# R212F.net
KiCad netlist of a schematic drawn in EAGLE
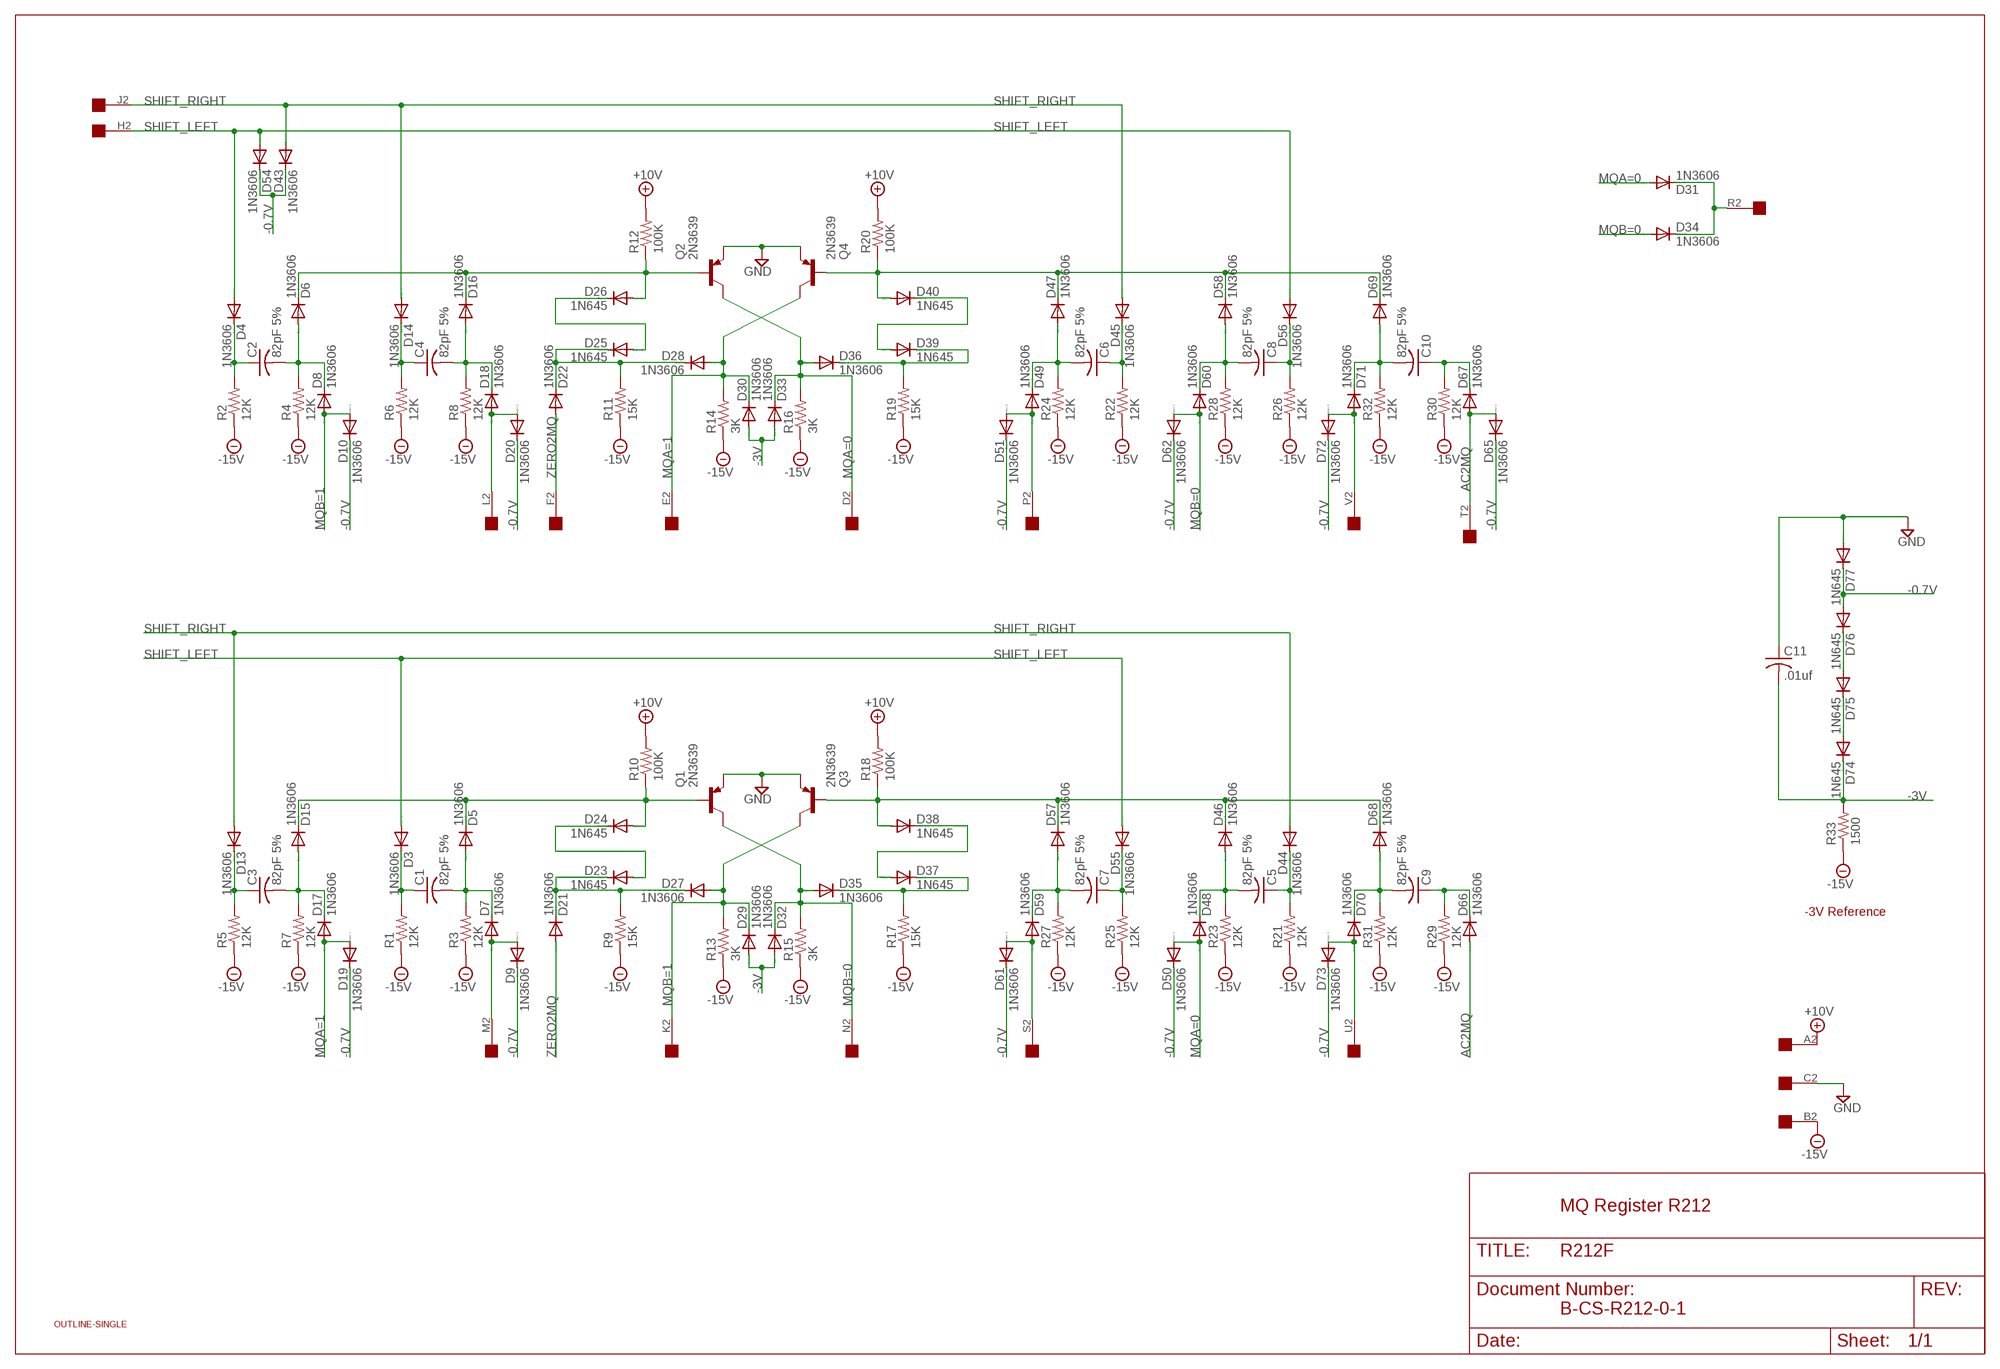
[diagram p0: schematic, sheet 1]

(export (version "E")
  (design (tool "Eeschema 10.0.6"))
  (components
    (comp (ref "C1")
      (value "82pF 5%")
      (footprint "eagle-import:C050-025X075")
      (libsource (lib "eagle-import") (part "C-US050-025X075"))
    )
    (comp (ref "C2")
      (value "82pF 5%")
      (footprint "eagle-import:C050-025X075")
      (libsource (lib "eagle-import") (part "C-US050-025X075"))
    )
    (comp (ref "C3")
      (value "82pF 5%")
      (footprint "eagle-import:C050-025X075")
      (libsource (lib "eagle-import") (part "C-US050-025X075"))
    )
    (comp (ref "C4")
      (value "82pF 5%")
      (footprint "eagle-import:C050-025X075")
      (libsource (lib "eagle-import") (part "C-US050-025X075"))
    )
    (comp (ref "C5")
      (value "82pF 5%")
      (footprint "eagle-import:C050-025X075")
      (libsource (lib "eagle-import") (part "C-US050-025X075"))
    )
    (comp (ref "C6")
      (value "82pF 5%")
      (footprint "eagle-import:C050-025X075")
      (libsource (lib "eagle-import") (part "C-US050-025X075"))
    )
    (comp (ref "C7")
      (value "82pF 5%")
      (footprint "eagle-import:C050-025X075")
      (libsource (lib "eagle-import") (part "C-US050-025X075"))
    )
    (comp (ref "C8")
      (value "82pF 5%")
      (footprint "eagle-import:C050-025X075")
      (libsource (lib "eagle-import") (part "C-US050-025X075"))
    )
    (comp (ref "C9")
      (value "82pF 5%")
      (footprint "eagle-import:C050-025X075")
      (libsource (lib "eagle-import") (part "C-US050-025X075"))
    )
    (comp (ref "C10")
      (value "82pF 5%")
      (footprint "eagle-import:C050-025X075")
      (libsource (lib "eagle-import") (part "C-US050-025X075"))
    )
    (comp (ref "C11")
      (value ".01uf")
      (footprint "eagle-import:C050-025X075")
      (libsource (lib "eagle-import") (part "C-US050-025X075"))
    )
    (comp (ref "D3")
      (value "1N3606")
      (footprint "eagle-import:DO35-10")
      (libsource (lib "eagle-import") (part "1N4148DO35-10"))
    )
    (comp (ref "D4")
      (value "1N3606")
      (footprint "eagle-import:DO35-10")
      (libsource (lib "eagle-import") (part "1N4148DO35-10"))
    )
    (comp (ref "D5")
      (value "1N3606")
      (footprint "eagle-import:DO35-10")
      (libsource (lib "eagle-import") (part "1N4148DO35-10"))
    )
    (comp (ref "D6")
      (value "1N3606")
      (footprint "eagle-import:DO35-10")
      (libsource (lib "eagle-import") (part "1N4148DO35-10"))
    )
    (comp (ref "D7")
      (value "1N3606")
      (footprint "eagle-import:DO35-10")
      (libsource (lib "eagle-import") (part "1N4148DO35-10"))
    )
    (comp (ref "D8")
      (value "1N3606")
      (footprint "eagle-import:DO35-10")
      (libsource (lib "eagle-import") (part "1N4148DO35-10"))
    )
    (comp (ref "D9")
      (value "1N3606")
      (footprint "eagle-import:DO35-10")
      (libsource (lib "eagle-import") (part "1N4148DO35-10"))
    )
    (comp (ref "D10")
      (value "1N3606")
      (footprint "eagle-import:DO35-10")
      (libsource (lib "eagle-import") (part "1N4148DO35-10"))
    )
    (comp (ref "D13")
      (value "1N3606")
      (footprint "eagle-import:DO35-10")
      (libsource (lib "eagle-import") (part "1N4148DO35-10"))
    )
    (comp (ref "D14")
      (value "1N3606")
      (footprint "eagle-import:DO35-10")
      (libsource (lib "eagle-import") (part "1N4148DO35-10"))
    )
    (comp (ref "D15")
      (value "1N3606")
      (footprint "eagle-import:DO35-10")
      (libsource (lib "eagle-import") (part "1N4148DO35-10"))
    )
    (comp (ref "D16")
      (value "1N3606")
      (footprint "eagle-import:DO35-10")
      (libsource (lib "eagle-import") (part "1N4148DO35-10"))
    )
    (comp (ref "D17")
      (value "1N3606")
      (footprint "eagle-import:DO35-10")
      (libsource (lib "eagle-import") (part "1N4148DO35-10"))
    )
    (comp (ref "D18")
      (value "1N3606")
      (footprint "eagle-import:DO35-10")
      (libsource (lib "eagle-import") (part "1N4148DO35-10"))
    )
    (comp (ref "D19")
      (value "1N3606")
      (footprint "eagle-import:DO35-10")
      (libsource (lib "eagle-import") (part "1N4148DO35-10"))
    )
    (comp (ref "D20")
      (value "1N3606")
      (footprint "eagle-import:DO35-10")
      (libsource (lib "eagle-import") (part "1N4148DO35-10"))
    )
    (comp (ref "D21")
      (value "1N3606")
      (footprint "eagle-import:DO35-10")
      (libsource (lib "eagle-import") (part "1N4148DO35-10"))
    )
    (comp (ref "D22")
      (value "1N3606")
      (footprint "eagle-import:DO35-10")
      (libsource (lib "eagle-import") (part "1N4148DO35-10"))
    )
    (comp (ref "D23")
      (value "1N645")
      (footprint "eagle-import:DO35-10")
      (libsource (lib "eagle-import") (part "1N4148DO35-10"))
    )
    (comp (ref "D24")
      (value "1N645")
      (footprint "eagle-import:DO35-10")
      (libsource (lib "eagle-import") (part "1N4148DO35-10"))
    )
    (comp (ref "D25")
      (value "1N645")
      (footprint "eagle-import:DO35-10")
      (libsource (lib "eagle-import") (part "1N4148DO35-10"))
    )
    (comp (ref "D26")
      (value "1N645")
      (footprint "eagle-import:DO35-10")
      (libsource (lib "eagle-import") (part "1N4148DO35-10"))
    )
    (comp (ref "D27")
      (value "1N3606")
      (footprint "eagle-import:DO35-10")
      (libsource (lib "eagle-import") (part "1N4148DO35-10"))
    )
    (comp (ref "D28")
      (value "1N3606")
      (footprint "eagle-import:DO35-10")
      (libsource (lib "eagle-import") (part "1N4148DO35-10"))
    )
    (comp (ref "D29")
      (value "1N3606")
      (footprint "eagle-import:DO35-10")
      (libsource (lib "eagle-import") (part "1N4148DO35-10"))
    )
    (comp (ref "D30")
      (value "1N3606")
      (footprint "eagle-import:DO35-10")
      (libsource (lib "eagle-import") (part "1N4148DO35-10"))
    )
    (comp (ref "D31")
      (value "1N3606")
      (footprint "eagle-import:DO35-10")
      (libsource (lib "eagle-import") (part "1N4148DO35-10"))
    )
    (comp (ref "D32")
      (value "1N3606")
      (footprint "eagle-import:DO35-10")
      (libsource (lib "eagle-import") (part "1N4148DO35-10"))
    )
    (comp (ref "D33")
      (value "1N3606")
      (footprint "eagle-import:DO35-10")
      (libsource (lib "eagle-import") (part "1N4148DO35-10"))
    )
    (comp (ref "D34")
      (value "1N3606")
      (footprint "eagle-import:DO35-10")
      (libsource (lib "eagle-import") (part "1N4148DO35-10"))
    )
    (comp (ref "D35")
      (value "1N3606")
      (footprint "eagle-import:DO35-10")
      (libsource (lib "eagle-import") (part "1N4148DO35-10"))
    )
    (comp (ref "D36")
      (value "1N3606")
      (footprint "eagle-import:DO35-10")
      (libsource (lib "eagle-import") (part "1N4148DO35-10"))
    )
    (comp (ref "D37")
      (value "1N645")
      (footprint "eagle-import:DO35-10")
      (libsource (lib "eagle-import") (part "1N4148DO35-10"))
    )
    (comp (ref "D38")
      (value "1N645")
      (footprint "eagle-import:DO35-10")
      (libsource (lib "eagle-import") (part "1N4148DO35-10"))
    )
    (comp (ref "D39")
      (value "1N645")
      (footprint "eagle-import:DO35-10")
      (libsource (lib "eagle-import") (part "1N4148DO35-10"))
    )
    (comp (ref "D40")
      (value "1N645")
      (footprint "eagle-import:DO35-10")
      (libsource (lib "eagle-import") (part "1N4148DO35-10"))
    )
    (comp (ref "D43")
      (value "1N3606")
      (footprint "eagle-import:DO35-10")
      (libsource (lib "eagle-import") (part "1N4148DO35-10"))
    )
    (comp (ref "D44")
      (value "1N3606")
      (footprint "eagle-import:DO35-10")
      (libsource (lib "eagle-import") (part "1N4148DO35-10"))
    )
    (comp (ref "D45")
      (value "1N3606")
      (footprint "eagle-import:DO35-10")
      (libsource (lib "eagle-import") (part "1N4148DO35-10"))
    )
    (comp (ref "D46")
      (value "1N3606")
      (footprint "eagle-import:DO35-10")
      (libsource (lib "eagle-import") (part "1N4148DO35-10"))
    )
    (comp (ref "D47")
      (value "1N3606")
      (footprint "eagle-import:DO35-10")
      (libsource (lib "eagle-import") (part "1N4148DO35-10"))
    )
    (comp (ref "D48")
      (value "1N3606")
      (footprint "eagle-import:DO35-10")
      (libsource (lib "eagle-import") (part "1N4148DO35-10"))
    )
    (comp (ref "D49")
      (value "1N3606")
      (footprint "eagle-import:DO35-10")
      (libsource (lib "eagle-import") (part "1N4148DO35-10"))
    )
    (comp (ref "D50")
      (value "1N3606")
      (footprint "eagle-import:DO35-10")
      (libsource (lib "eagle-import") (part "1N4148DO35-10"))
    )
    (comp (ref "D51")
      (value "1N3606")
      (footprint "eagle-import:DO35-10")
      (libsource (lib "eagle-import") (part "1N4148DO35-10"))
    )
    (comp (ref "D54")
      (value "1N3606")
      (footprint "eagle-import:DO35-10")
      (libsource (lib "eagle-import") (part "1N4148DO35-10"))
    )
    (comp (ref "D55")
      (value "1N3606")
      (footprint "eagle-import:DO35-10")
      (libsource (lib "eagle-import") (part "1N4148DO35-10"))
    )
    (comp (ref "D56")
      (value "1N3606")
      (footprint "eagle-import:DO35-10")
      (libsource (lib "eagle-import") (part "1N4148DO35-10"))
    )
    (comp (ref "D57")
      (value "1N3606")
      (footprint "eagle-import:DO35-10")
      (libsource (lib "eagle-import") (part "1N4148DO35-10"))
    )
    (comp (ref "D58")
      (value "1N3606")
      (footprint "eagle-import:DO35-10")
      (libsource (lib "eagle-import") (part "1N4148DO35-10"))
    )
    (comp (ref "D59")
      (value "1N3606")
      (footprint "eagle-import:DO35-10")
      (libsource (lib "eagle-import") (part "1N4148DO35-10"))
    )
    (comp (ref "D60")
      (value "1N3606")
      (footprint "eagle-import:DO35-10")
      (libsource (lib "eagle-import") (part "1N4148DO35-10"))
    )
    (comp (ref "D61")
      (value "1N3606")
      (footprint "eagle-import:DO35-10")
      (libsource (lib "eagle-import") (part "1N4148DO35-10"))
    )
    (comp (ref "D62")
      (value "1N3606")
      (footprint "eagle-import:DO35-10")
      (libsource (lib "eagle-import") (part "1N4148DO35-10"))
    )
    (comp (ref "D65")
      (value "1N3606")
      (footprint "eagle-import:DO35-10")
      (libsource (lib "eagle-import") (part "1N4148DO35-10"))
    )
    (comp (ref "D66")
      (value "1N3606")
      (footprint "eagle-import:DO35-10")
      (libsource (lib "eagle-import") (part "1N4148DO35-10"))
    )
    (comp (ref "D67")
      (value "1N3606")
      (footprint "eagle-import:DO35-10")
      (libsource (lib "eagle-import") (part "1N4148DO35-10"))
    )
    (comp (ref "D68")
      (value "1N3606")
      (footprint "eagle-import:DO35-10")
      (libsource (lib "eagle-import") (part "1N4148DO35-10"))
    )
    (comp (ref "D69")
      (value "1N3606")
      (footprint "eagle-import:DO35-10")
      (libsource (lib "eagle-import") (part "1N4148DO35-10"))
    )
    (comp (ref "D70")
      (value "1N3606")
      (footprint "eagle-import:DO35-10")
      (libsource (lib "eagle-import") (part "1N4148DO35-10"))
    )
    (comp (ref "D71")
      (value "1N3606")
      (footprint "eagle-import:DO35-10")
      (libsource (lib "eagle-import") (part "1N4148DO35-10"))
    )
    (comp (ref "D72")
      (value "1N3606")
      (footprint "eagle-import:DO35-10")
      (libsource (lib "eagle-import") (part "1N4148DO35-10"))
    )
    (comp (ref "D73")
      (value "1N3606")
      (footprint "eagle-import:DO35-10")
      (libsource (lib "eagle-import") (part "1N4148DO35-10"))
    )
    (comp (ref "D74")
      (value "1N645")
      (footprint "eagle-import:DO35-10")
      (libsource (lib "eagle-import") (part "1N4148DO35-10"))
    )
    (comp (ref "D75")
      (value "1N645")
      (footprint "eagle-import:DO35-10")
      (libsource (lib "eagle-import") (part "1N4148DO35-10"))
    )
    (comp (ref "D76")
      (value "1N645")
      (footprint "eagle-import:DO35-10")
      (libsource (lib "eagle-import") (part "1N4148DO35-10"))
    )
    (comp (ref "D77")
      (value "1N645")
      (footprint "eagle-import:DO35-10")
      (libsource (lib "eagle-import") (part "1N4148DO35-10"))
    )
    (comp (ref "Q1")
      (value "2N3639")
      (footprint "eagle-import:TO39")
      (libsource (lib "eagle-import") (part "2N3637"))
    )
    (comp (ref "Q2")
      (value "2N3639")
      (footprint "eagle-import:TO39")
      (libsource (lib "eagle-import") (part "2N3637"))
    )
    (comp (ref "Q3")
      (value "2N3639")
      (footprint "eagle-import:TO39")
      (libsource (lib "eagle-import") (part "2N3637"))
    )
    (comp (ref "Q4")
      (value "2N3639")
      (footprint "eagle-import:TO39")
      (libsource (lib "eagle-import") (part "2N3637"))
    )
    (comp (ref "R1")
      (value "12K")
      (footprint "eagle-import:0207_10")
      (libsource (lib "eagle-import") (part "R-US_0207/10"))
    )
    (comp (ref "R2")
      (value "12K")
      (footprint "eagle-import:0207_10")
      (libsource (lib "eagle-import") (part "R-US_0207/10"))
    )
    (comp (ref "R3")
      (value "12K")
      (footprint "eagle-import:0207_10")
      (libsource (lib "eagle-import") (part "R-US_0207/10"))
    )
    (comp (ref "R4")
      (value "12K")
      (footprint "eagle-import:0207_10")
      (libsource (lib "eagle-import") (part "R-US_0207/10"))
    )
    (comp (ref "R5")
      (value "12K")
      (footprint "eagle-import:0207_10")
      (libsource (lib "eagle-import") (part "R-US_0207/10"))
    )
    (comp (ref "R6")
      (value "12K")
      (footprint "eagle-import:0207_10")
      (libsource (lib "eagle-import") (part "R-US_0207/10"))
    )
    (comp (ref "R7")
      (value "12K")
      (footprint "eagle-import:0207_10")
      (libsource (lib "eagle-import") (part "R-US_0207/10"))
    )
    (comp (ref "R8")
      (value "12K")
      (footprint "eagle-import:0207_10")
      (libsource (lib "eagle-import") (part "R-US_0207/10"))
    )
    (comp (ref "R9")
      (value "15K")
      (footprint "eagle-import:0207_10")
      (libsource (lib "eagle-import") (part "R-US_0207/10"))
    )
    (comp (ref "R10")
      (value "100K")
      (footprint "eagle-import:0207_10")
      (libsource (lib "eagle-import") (part "R-US_0207/10"))
    )
    (comp (ref "R11")
      (value "15K")
      (footprint "eagle-import:0207_10")
      (libsource (lib "eagle-import") (part "R-US_0207/10"))
    )
    (comp (ref "R12")
      (value "100K")
      (footprint "eagle-import:0207_10")
      (libsource (lib "eagle-import") (part "R-US_0207/10"))
    )
    (comp (ref "R13")
      (value "3K")
      (footprint "eagle-import:0207_10")
      (libsource (lib "eagle-import") (part "R-US_0207/10"))
    )
    (comp (ref "R14")
      (value "3K")
      (footprint "eagle-import:0207_10")
      (libsource (lib "eagle-import") (part "R-US_0207/10"))
    )
    (comp (ref "R15")
      (value "3K")
      (footprint "eagle-import:0207_10")
      (libsource (lib "eagle-import") (part "R-US_0207/10"))
    )
    (comp (ref "R16")
      (value "3K")
      (footprint "eagle-import:0207_10")
      (libsource (lib "eagle-import") (part "R-US_0207/10"))
    )
    (comp (ref "R17")
      (value "15K")
      (footprint "eagle-import:0207_10")
      (libsource (lib "eagle-import") (part "R-US_0207/10"))
    )
    (comp (ref "R18")
      (value "100K")
      (footprint "eagle-import:0207_10")
      (libsource (lib "eagle-import") (part "R-US_0207/10"))
    )
    (comp (ref "R19")
      (value "15K")
      (footprint "eagle-import:0207_10")
      (libsource (lib "eagle-import") (part "R-US_0207/10"))
    )
    (comp (ref "R20")
      (value "100K")
      (footprint "eagle-import:0207_10")
      (libsource (lib "eagle-import") (part "R-US_0207/10"))
    )
    (comp (ref "R21")
      (value "12K")
      (footprint "eagle-import:0207_10")
      (libsource (lib "eagle-import") (part "R-US_0207/10"))
    )
    (comp (ref "R22")
      (value "12K")
      (footprint "eagle-import:0207_10")
      (libsource (lib "eagle-import") (part "R-US_0207/10"))
    )
    (comp (ref "R23")
      (value "12K")
      (footprint "eagle-import:0207_10")
      (libsource (lib "eagle-import") (part "R-US_0207/10"))
    )
    (comp (ref "R24")
      (value "12K")
      (footprint "eagle-import:0207_10")
      (libsource (lib "eagle-import") (part "R-US_0207/10"))
    )
    (comp (ref "R25")
      (value "12K")
      (footprint "eagle-import:0207_10")
      (libsource (lib "eagle-import") (part "R-US_0207/10"))
    )
    (comp (ref "R26")
      (value "12K")
      (footprint "eagle-import:0207_10")
      (libsource (lib "eagle-import") (part "R-US_0207/10"))
    )
    (comp (ref "R27")
      (value "12K")
      (footprint "eagle-import:0207_10")
      (libsource (lib "eagle-import") (part "R-US_0207/10"))
    )
    (comp (ref "R28")
      (value "12K")
      (footprint "eagle-import:0207_10")
      (libsource (lib "eagle-import") (part "R-US_0207/10"))
    )
    (comp (ref "R29")
      (value "12K")
      (footprint "eagle-import:0207_10")
      (libsource (lib "eagle-import") (part "R-US_0207/10"))
    )
    (comp (ref "R30")
      (value "12K")
      (footprint "eagle-import:0207_10")
      (libsource (lib "eagle-import") (part "R-US_0207/10"))
    )
    (comp (ref "R31")
      (value "12K")
      (footprint "eagle-import:0207_10")
      (libsource (lib "eagle-import") (part "R-US_0207/10"))
    )
    (comp (ref "R32")
      (value "12K")
      (footprint "eagle-import:0207_10")
      (libsource (lib "eagle-import") (part "R-US_0207/10"))
    )
    (comp (ref "R33")
      (value "1500")
      (footprint "eagle-import:0207_10")
      (libsource (lib "eagle-import") (part "R-US_0207/10"))
    )
    (comp (ref "U$1")
      (value "OUTLINE-SINGLE")
      (footprint "eagle-import:SINGLE")
      (libsource (lib "eagle-import") (part "OUTLINE-SINGLE"))
    )
    (comp (ref "U$2")
      (value "EDGE-1")
      (footprint "eagle-import:EDGE-CON1")
      (libsource (lib "eagle-import") (part "EDGE-1"))
    )
  )
  (nets
    (net (code "1") (name "+10V") (class "Default")
      (node (ref "R10") (pin "2") (pinfunction "2_2") (pintype "passive"))
      (node (ref "R12") (pin "2") (pinfunction "2_2") (pintype "passive"))
      (node (ref "R18") (pin "2") (pinfunction "2_2") (pintype "passive"))
      (node (ref "R20") (pin "2") (pinfunction "2_2") (pintype "passive"))
      (node (ref "U$2") (pin "A2") (pinfunction "1_A2") (pintype "bidirectional"))
    )
    (net (code "2") (name "-15V") (class "Default")
      (node (ref "R1") (pin "1") (pinfunction "1_1") (pintype "passive"))
      (node (ref "R11") (pin "1") (pinfunction "1_1") (pintype "passive"))
      (node (ref "R13") (pin "1") (pinfunction "1_1") (pintype "passive"))
      (node (ref "R14") (pin "1") (pinfunction "1_1") (pintype "passive"))
      (node (ref "R15") (pin "1") (pinfunction "1_1") (pintype "passive"))
      (node (ref "R16") (pin "1") (pinfunction "1_1") (pintype "passive"))
      (node (ref "R17") (pin "1") (pinfunction "1_1") (pintype "passive"))
      (node (ref "R19") (pin "1") (pinfunction "1_1") (pintype "passive"))
      (node (ref "R2") (pin "1") (pinfunction "1_1") (pintype "passive"))
      (node (ref "R21") (pin "1") (pinfunction "1_1") (pintype "passive"))
      (node (ref "R22") (pin "1") (pinfunction "1_1") (pintype "passive"))
      (node (ref "R23") (pin "1") (pinfunction "1_1") (pintype "passive"))
      (node (ref "R24") (pin "1") (pinfunction "1_1") (pintype "passive"))
      (node (ref "R25") (pin "1") (pinfunction "1_1") (pintype "passive"))
      (node (ref "R26") (pin "1") (pinfunction "1_1") (pintype "passive"))
      (node (ref "R27") (pin "1") (pinfunction "1_1") (pintype "passive"))
      (node (ref "R28") (pin "1") (pinfunction "1_1") (pintype "passive"))
      (node (ref "R29") (pin "1") (pinfunction "1_1") (pintype "passive"))
      (node (ref "R3") (pin "1") (pinfunction "1_1") (pintype "passive"))
      (node (ref "R30") (pin "1") (pinfunction "1_1") (pintype "passive"))
      (node (ref "R31") (pin "1") (pinfunction "1_1") (pintype "passive"))
      (node (ref "R32") (pin "1") (pinfunction "1_1") (pintype "passive"))
      (node (ref "R33") (pin "1") (pinfunction "1_1") (pintype "passive"))
      (node (ref "R4") (pin "1") (pinfunction "1_1") (pintype "passive"))
      (node (ref "R5") (pin "1") (pinfunction "1_1") (pintype "passive"))
      (node (ref "R6") (pin "1") (pinfunction "1_1") (pintype "passive"))
      (node (ref "R7") (pin "1") (pinfunction "1_1") (pintype "passive"))
      (node (ref "R8") (pin "1") (pinfunction "1_1") (pintype "passive"))
      (node (ref "R9") (pin "1") (pinfunction "1_1") (pintype "passive"))
      (node (ref "U$2") (pin "B2") (pinfunction "1_B2") (pintype "bidirectional"))
    )
    (net (code "3") (name "/-0.7V") (class "Default")
      (node (ref "D10") (pin "C") (pinfunction "C_C") (pintype "passive"))
      (node (ref "D19") (pin "C") (pinfunction "C_C") (pintype "passive"))
      (node (ref "D20") (pin "C") (pinfunction "C_C") (pintype "passive"))
      (node (ref "D43") (pin "C") (pinfunction "C_C") (pintype "passive"))
      (node (ref "D50") (pin "C") (pinfunction "C_C") (pintype "passive"))
      (node (ref "D51") (pin "C") (pinfunction "C_C") (pintype "passive"))
      (node (ref "D54") (pin "C") (pinfunction "C_C") (pintype "passive"))
      (node (ref "D61") (pin "C") (pinfunction "C_C") (pintype "passive"))
      (node (ref "D62") (pin "C") (pinfunction "C_C") (pintype "passive"))
      (node (ref "D65") (pin "C") (pinfunction "C_C") (pintype "passive"))
      (node (ref "D72") (pin "C") (pinfunction "C_C") (pintype "passive"))
      (node (ref "D73") (pin "C") (pinfunction "C_C") (pintype "passive"))
      (node (ref "D76") (pin "A") (pinfunction "A_A") (pintype "passive"))
      (node (ref "D77") (pin "C") (pinfunction "C_C") (pintype "passive"))
      (node (ref "D9") (pin "C") (pinfunction "C_C") (pintype "passive"))
    )
    (net (code "4") (name "/-3V") (class "Default")
      (node (ref "C11") (pin "2") (pinfunction "2_2") (pintype "passive"))
      (node (ref "D29") (pin "A") (pinfunction "A_A") (pintype "passive"))
      (node (ref "D30") (pin "A") (pinfunction "A_A") (pintype "passive"))
      (node (ref "D32") (pin "A") (pinfunction "A_A") (pintype "passive"))
      (node (ref "D33") (pin "A") (pinfunction "A_A") (pintype "passive"))
      (node (ref "D74") (pin "C") (pinfunction "C_C") (pintype "passive"))
      (node (ref "R33") (pin "2") (pinfunction "2_2") (pintype "passive"))
    )
    (net (code "5") (name "/AC2MQ") (class "Default")
      (node (ref "D65") (pin "A") (pinfunction "A_A") (pintype "passive"))
      (node (ref "D66") (pin "A") (pinfunction "A_A") (pintype "passive"))
      (node (ref "D67") (pin "A") (pinfunction "A_A") (pintype "passive"))
      (node (ref "U$2") (pin "T2") (pinfunction "1_T2") (pintype "bidirectional"))
    )
    (net (code "6") (name "/MQA=0") (class "Default")
      (node (ref "D31") (pin "A") (pinfunction "A_A") (pintype "passive"))
      (node (ref "D33") (pin "C") (pinfunction "C_C") (pintype "passive"))
      (node (ref "D36") (pin "A") (pinfunction "A_A") (pintype "passive"))
      (node (ref "D48") (pin "A") (pinfunction "A_A") (pintype "passive"))
      (node (ref "D50") (pin "A") (pinfunction "A_A") (pintype "passive"))
      (node (ref "Q2") (pin "3") (pinfunction "C_3") (pintype "passive"))
      (node (ref "R16") (pin "2") (pinfunction "2_2") (pintype "passive"))
      (node (ref "U$2") (pin "D2") (pinfunction "1_D2") (pintype "bidirectional"))
    )
    (net (code "7") (name "/MQA=1") (class "Default")
      (node (ref "D17") (pin "A") (pinfunction "A_A") (pintype "passive"))
      (node (ref "D19") (pin "A") (pinfunction "A_A") (pintype "passive"))
      (node (ref "D28") (pin "A") (pinfunction "A_A") (pintype "passive"))
      (node (ref "D30") (pin "C") (pinfunction "C_C") (pintype "passive"))
      (node (ref "Q4") (pin "3") (pinfunction "C_3") (pintype "passive"))
      (node (ref "R14") (pin "2") (pinfunction "2_2") (pintype "passive"))
      (node (ref "U$2") (pin "E2") (pinfunction "1_E2") (pintype "bidirectional"))
    )
    (net (code "8") (name "/MQB=0") (class "Default")
      (node (ref "D32") (pin "C") (pinfunction "C_C") (pintype "passive"))
      (node (ref "D34") (pin "A") (pinfunction "A_A") (pintype "passive"))
      (node (ref "D35") (pin "A") (pinfunction "A_A") (pintype "passive"))
      (node (ref "D60") (pin "A") (pinfunction "A_A") (pintype "passive"))
      (node (ref "D62") (pin "A") (pinfunction "A_A") (pintype "passive"))
      (node (ref "Q1") (pin "3") (pinfunction "C_3") (pintype "passive"))
      (node (ref "R15") (pin "2") (pinfunction "2_2") (pintype "passive"))
      (node (ref "U$2") (pin "N2") (pinfunction "1_N2") (pintype "bidirectional"))
    )
    (net (code "9") (name "/MQB=1") (class "Default")
      (node (ref "D10") (pin "A") (pinfunction "A_A") (pintype "passive"))
      (node (ref "D27") (pin "A") (pinfunction "A_A") (pintype "passive"))
      (node (ref "D29") (pin "C") (pinfunction "C_C") (pintype "passive"))
      (node (ref "D8") (pin "A") (pinfunction "A_A") (pintype "passive"))
      (node (ref "Q3") (pin "3") (pinfunction "C_3") (pintype "passive"))
      (node (ref "R13") (pin "2") (pinfunction "2_2") (pintype "passive"))
      (node (ref "U$2") (pin "K2") (pinfunction "1_K2") (pintype "bidirectional"))
    )
    (net (code "10") (name "/SHIFT_LEFT") (class "Default")
      (node (ref "D3") (pin "A") (pinfunction "A_A") (pintype "passive"))
      (node (ref "D4") (pin "A") (pinfunction "A_A") (pintype "passive"))
      (node (ref "D54") (pin "A") (pinfunction "A_A") (pintype "passive"))
      (node (ref "D55") (pin "A") (pinfunction "A_A") (pintype "passive"))
      (node (ref "D56") (pin "A") (pinfunction "A_A") (pintype "passive"))
      (node (ref "U$2") (pin "H2") (pinfunction "1_H2") (pintype "bidirectional"))
    )
    (net (code "11") (name "/SHIFT_RIGHT") (class "Default")
      (node (ref "D13") (pin "A") (pinfunction "A_A") (pintype "passive"))
      (node (ref "D14") (pin "A") (pinfunction "A_A") (pintype "passive"))
      (node (ref "D43") (pin "A") (pinfunction "A_A") (pintype "passive"))
      (node (ref "D44") (pin "A") (pinfunction "A_A") (pintype "passive"))
      (node (ref "D45") (pin "A") (pinfunction "A_A") (pintype "passive"))
      (node (ref "U$2") (pin "J2") (pinfunction "1_J2") (pintype "bidirectional"))
    )
    (net (code "12") (name "/ZERO2MQ") (class "Default")
      (node (ref "D21") (pin "A") (pinfunction "A_A") (pintype "passive"))
      (node (ref "D22") (pin "A") (pinfunction "A_A") (pintype "passive"))
      (node (ref "U$2") (pin "F2") (pinfunction "1_F2") (pintype "bidirectional"))
    )
    (net (code "13") (name "GND") (class "Default")
      (node (ref "C11") (pin "1") (pinfunction "1_1") (pintype "passive"))
      (node (ref "D77") (pin "A") (pinfunction "A_A") (pintype "passive"))
      (node (ref "Q1") (pin "1") (pinfunction "E_1") (pintype "passive"))
      (node (ref "Q2") (pin "1") (pinfunction "E_1") (pintype "passive"))
      (node (ref "Q3") (pin "1") (pinfunction "E_1") (pintype "passive"))
      (node (ref "Q4") (pin "1") (pinfunction "E_1") (pintype "passive"))
      (node (ref "U$2") (pin "C2") (pinfunction "1_C2") (pintype "bidirectional"))
    )
    (net (code "14") (name "Net-(C1-Pad1)") (class "Default")
      (node (ref "C1") (pin "1") (pinfunction "1_1") (pintype "passive"))
      (node (ref "D3") (pin "C") (pinfunction "C_C") (pintype "passive"))
      (node (ref "R1") (pin "2") (pinfunction "2_2") (pintype "passive"))
    )
    (net (code "15") (name "Net-(C1-Pad2)") (class "Default")
      (node (ref "C1") (pin "2") (pinfunction "2_2") (pintype "passive"))
      (node (ref "D5") (pin "A") (pinfunction "A_A") (pintype "passive"))
      (node (ref "D7") (pin "C") (pinfunction "C_C") (pintype "passive"))
      (node (ref "R3") (pin "2") (pinfunction "2_2") (pintype "passive"))
    )
    (net (code "16") (name "Net-(C2-Pad1)") (class "Default")
      (node (ref "C2") (pin "1") (pinfunction "1_1") (pintype "passive"))
      (node (ref "D4") (pin "C") (pinfunction "C_C") (pintype "passive"))
      (node (ref "R2") (pin "2") (pinfunction "2_2") (pintype "passive"))
    )
    (net (code "17") (name "Net-(C2-Pad2)") (class "Default")
      (node (ref "C2") (pin "2") (pinfunction "2_2") (pintype "passive"))
      (node (ref "D6") (pin "A") (pinfunction "A_A") (pintype "passive"))
      (node (ref "D8") (pin "C") (pinfunction "C_C") (pintype "passive"))
      (node (ref "R4") (pin "2") (pinfunction "2_2") (pintype "passive"))
    )
    (net (code "18") (name "Net-(C3-Pad1)") (class "Default")
      (node (ref "C3") (pin "1") (pinfunction "1_1") (pintype "passive"))
      (node (ref "D13") (pin "C") (pinfunction "C_C") (pintype "passive"))
      (node (ref "R5") (pin "2") (pinfunction "2_2") (pintype "passive"))
    )
    (net (code "19") (name "Net-(C3-Pad2)") (class "Default")
      (node (ref "C3") (pin "2") (pinfunction "2_2") (pintype "passive"))
      (node (ref "D15") (pin "A") (pinfunction "A_A") (pintype "passive"))
      (node (ref "D17") (pin "C") (pinfunction "C_C") (pintype "passive"))
      (node (ref "R7") (pin "2") (pinfunction "2_2") (pintype "passive"))
    )
    (net (code "20") (name "Net-(C4-Pad1)") (class "Default")
      (node (ref "C4") (pin "1") (pinfunction "1_1") (pintype "passive"))
      (node (ref "D14") (pin "C") (pinfunction "C_C") (pintype "passive"))
      (node (ref "R6") (pin "2") (pinfunction "2_2") (pintype "passive"))
    )
    (net (code "21") (name "Net-(C4-Pad2)") (class "Default")
      (node (ref "C4") (pin "2") (pinfunction "2_2") (pintype "passive"))
      (node (ref "D16") (pin "A") (pinfunction "A_A") (pintype "passive"))
      (node (ref "D18") (pin "C") (pinfunction "C_C") (pintype "passive"))
      (node (ref "R8") (pin "2") (pinfunction "2_2") (pintype "passive"))
    )
    (net (code "22") (name "Net-(C5-Pad1)") (class "Default")
      (node (ref "C5") (pin "1") (pinfunction "1_1") (pintype "passive"))
      (node (ref "D44") (pin "C") (pinfunction "C_C") (pintype "passive"))
      (node (ref "R21") (pin "2") (pinfunction "2_2") (pintype "passive"))
    )
    (net (code "23") (name "Net-(C5-Pad2)") (class "Default")
      (node (ref "C5") (pin "2") (pinfunction "2_2") (pintype "passive"))
      (node (ref "D46") (pin "A") (pinfunction "A_A") (pintype "passive"))
      (node (ref "D48") (pin "C") (pinfunction "C_C") (pintype "passive"))
      (node (ref "R23") (pin "2") (pinfunction "2_2") (pintype "passive"))
    )
    (net (code "24") (name "Net-(C6-Pad1)") (class "Default")
      (node (ref "C6") (pin "1") (pinfunction "1_1") (pintype "passive"))
      (node (ref "D45") (pin "C") (pinfunction "C_C") (pintype "passive"))
      (node (ref "R22") (pin "2") (pinfunction "2_2") (pintype "passive"))
    )
    (net (code "25") (name "Net-(C6-Pad2)") (class "Default")
      (node (ref "C6") (pin "2") (pinfunction "2_2") (pintype "passive"))
      (node (ref "D47") (pin "A") (pinfunction "A_A") (pintype "passive"))
      (node (ref "D49") (pin "C") (pinfunction "C_C") (pintype "passive"))
      (node (ref "R24") (pin "2") (pinfunction "2_2") (pintype "passive"))
    )
    (net (code "26") (name "Net-(C7-Pad1)") (class "Default")
      (node (ref "C7") (pin "1") (pinfunction "1_1") (pintype "passive"))
      (node (ref "D55") (pin "C") (pinfunction "C_C") (pintype "passive"))
      (node (ref "R25") (pin "2") (pinfunction "2_2") (pintype "passive"))
    )
    (net (code "27") (name "Net-(C7-Pad2)") (class "Default")
      (node (ref "C7") (pin "2") (pinfunction "2_2") (pintype "passive"))
      (node (ref "D57") (pin "A") (pinfunction "A_A") (pintype "passive"))
      (node (ref "D59") (pin "C") (pinfunction "C_C") (pintype "passive"))
      (node (ref "R27") (pin "2") (pinfunction "2_2") (pintype "passive"))
    )
    (net (code "28") (name "Net-(C8-Pad1)") (class "Default")
      (node (ref "C8") (pin "1") (pinfunction "1_1") (pintype "passive"))
      (node (ref "D56") (pin "C") (pinfunction "C_C") (pintype "passive"))
      (node (ref "R26") (pin "2") (pinfunction "2_2") (pintype "passive"))
    )
    (net (code "29") (name "Net-(C8-Pad2)") (class "Default")
      (node (ref "C8") (pin "2") (pinfunction "2_2") (pintype "passive"))
      (node (ref "D58") (pin "A") (pinfunction "A_A") (pintype "passive"))
      (node (ref "D60") (pin "C") (pinfunction "C_C") (pintype "passive"))
      (node (ref "R28") (pin "2") (pinfunction "2_2") (pintype "passive"))
    )
    (net (code "30") (name "Net-(C9-Pad1)") (class "Default")
      (node (ref "C9") (pin "1") (pinfunction "1_1") (pintype "passive"))
      (node (ref "D66") (pin "C") (pinfunction "C_C") (pintype "passive"))
      (node (ref "R29") (pin "2") (pinfunction "2_2") (pintype "passive"))
    )
    (net (code "31") (name "Net-(C9-Pad2)") (class "Default")
      (node (ref "C9") (pin "2") (pinfunction "2_2") (pintype "passive"))
      (node (ref "D68") (pin "A") (pinfunction "A_A") (pintype "passive"))
      (node (ref "D70") (pin "C") (pinfunction "C_C") (pintype "passive"))
      (node (ref "R31") (pin "2") (pinfunction "2_2") (pintype "passive"))
    )
    (net (code "32") (name "Net-(C10-Pad1)") (class "Default")
      (node (ref "C10") (pin "1") (pinfunction "1_1") (pintype "passive"))
      (node (ref "D67") (pin "C") (pinfunction "C_C") (pintype "passive"))
      (node (ref "R30") (pin "2") (pinfunction "2_2") (pintype "passive"))
    )
    (net (code "33") (name "Net-(C10-Pad2)") (class "Default")
      (node (ref "C10") (pin "2") (pinfunction "2_2") (pintype "passive"))
      (node (ref "D69") (pin "A") (pinfunction "A_A") (pintype "passive"))
      (node (ref "D71") (pin "C") (pinfunction "C_C") (pintype "passive"))
      (node (ref "R32") (pin "2") (pinfunction "2_2") (pintype "passive"))
    )
    (net (code "34") (name "Net-(D21-PadC)") (class "Default")
      (node (ref "D21") (pin "C") (pinfunction "C_C") (pintype "passive"))
      (node (ref "D23") (pin "C") (pinfunction "C_C") (pintype "passive"))
      (node (ref "D27") (pin "C") (pinfunction "C_C") (pintype "passive"))
      (node (ref "R9") (pin "2") (pinfunction "2_2") (pintype "passive"))
    )
    (net (code "35") (name "Net-(D22-PadC)") (class "Default")
      (node (ref "D22") (pin "C") (pinfunction "C_C") (pintype "passive"))
      (node (ref "D25") (pin "C") (pinfunction "C_C") (pintype "passive"))
      (node (ref "D28") (pin "C") (pinfunction "C_C") (pintype "passive"))
      (node (ref "R11") (pin "2") (pinfunction "2_2") (pintype "passive"))
    )
    (net (code "36") (name "Net-(D23-PadA)") (class "Default")
      (node (ref "D23") (pin "A") (pinfunction "A_A") (pintype "passive"))
      (node (ref "D24") (pin "C") (pinfunction "C_C") (pintype "passive"))
    )
    (net (code "37") (name "Net-(D25-PadA)") (class "Default")
      (node (ref "D25") (pin "A") (pinfunction "A_A") (pintype "passive"))
      (node (ref "D26") (pin "C") (pinfunction "C_C") (pintype "passive"))
    )
    (net (code "38") (name "Net-(D35-PadC)") (class "Default")
      (node (ref "D35") (pin "C") (pinfunction "C_C") (pintype "passive"))
      (node (ref "D37") (pin "C") (pinfunction "C_C") (pintype "passive"))
      (node (ref "R17") (pin "2") (pinfunction "2_2") (pintype "passive"))
    )
    (net (code "39") (name "Net-(D36-PadC)") (class "Default")
      (node (ref "D36") (pin "C") (pinfunction "C_C") (pintype "passive"))
      (node (ref "D39") (pin "C") (pinfunction "C_C") (pintype "passive"))
      (node (ref "R19") (pin "2") (pinfunction "2_2") (pintype "passive"))
    )
    (net (code "40") (name "Net-(D37-PadA)") (class "Default")
      (node (ref "D37") (pin "A") (pinfunction "A_A") (pintype "passive"))
      (node (ref "D38") (pin "C") (pinfunction "C_C") (pintype "passive"))
    )
    (net (code "41") (name "Net-(D39-PadA)") (class "Default")
      (node (ref "D39") (pin "A") (pinfunction "A_A") (pintype "passive"))
      (node (ref "D40") (pin "C") (pinfunction "C_C") (pintype "passive"))
    )
    (net (code "42") (name "Net-(D74-PadA)") (class "Default")
      (node (ref "D74") (pin "A") (pinfunction "A_A") (pintype "passive"))
      (node (ref "D75") (pin "C") (pinfunction "C_C") (pintype "passive"))
    )
    (net (code "43") (name "Net-(D75-PadA)") (class "Default")
      (node (ref "D75") (pin "A") (pinfunction "A_A") (pintype "passive"))
      (node (ref "D76") (pin "C") (pinfunction "C_C") (pintype "passive"))
    )
    (net (code "44") (name "Net-(Q1-B)") (class "Default")
      (node (ref "D15") (pin "C") (pinfunction "C_C") (pintype "passive"))
      (node (ref "D24") (pin "A") (pinfunction "A_A") (pintype "passive"))
      (node (ref "D5") (pin "C") (pinfunction "C_C") (pintype "passive"))
      (node (ref "Q1") (pin "2") (pinfunction "B_2") (pintype "passive"))
      (node (ref "R10") (pin "1") (pinfunction "1_1") (pintype "passive"))
    )
    (net (code "45") (name "Net-(Q2-B)") (class "Default")
      (node (ref "D16") (pin "C") (pinfunction "C_C") (pintype "passive"))
      (node (ref "D26") (pin "A") (pinfunction "A_A") (pintype "passive"))
      (node (ref "D6") (pin "C") (pinfunction "C_C") (pintype "passive"))
      (node (ref "Q2") (pin "2") (pinfunction "B_2") (pintype "passive"))
      (node (ref "R12") (pin "1") (pinfunction "1_1") (pintype "passive"))
    )
    (net (code "46") (name "Net-(Q3-B)") (class "Default")
      (node (ref "D38") (pin "A") (pinfunction "A_A") (pintype "passive"))
      (node (ref "D46") (pin "C") (pinfunction "C_C") (pintype "passive"))
      (node (ref "D57") (pin "C") (pinfunction "C_C") (pintype "passive"))
      (node (ref "D68") (pin "C") (pinfunction "C_C") (pintype "passive"))
      (node (ref "Q3") (pin "2") (pinfunction "B_2") (pintype "passive"))
      (node (ref "R18") (pin "1") (pinfunction "1_1") (pintype "passive"))
    )
    (net (code "47") (name "Net-(Q4-B)") (class "Default")
      (node (ref "D40") (pin "A") (pinfunction "A_A") (pintype "passive"))
      (node (ref "D47") (pin "C") (pinfunction "C_C") (pintype "passive"))
      (node (ref "D58") (pin "C") (pinfunction "C_C") (pintype "passive"))
      (node (ref "D69") (pin "C") (pinfunction "C_C") (pintype "passive"))
      (node (ref "Q4") (pin "2") (pinfunction "B_2") (pintype "passive"))
      (node (ref "R20") (pin "1") (pinfunction "1_1") (pintype "passive"))
    )
    (net (code "48") (name "Net-(U$2J-1)") (class "Default")
      (node (ref "D18") (pin "A") (pinfunction "A_A") (pintype "passive"))
      (node (ref "D20") (pin "A") (pinfunction "A_A") (pintype "passive"))
      (node (ref "U$2") (pin "L2") (pinfunction "1_L2") (pintype "bidirectional"))
    )
    (net (code "49") (name "Net-(U$2K-1)") (class "Default")
      (node (ref "D7") (pin "A") (pinfunction "A_A") (pintype "passive"))
      (node (ref "D9") (pin "A") (pinfunction "A_A") (pintype "passive"))
      (node (ref "U$2") (pin "M2") (pinfunction "1_M2") (pintype "bidirectional"))
    )
    (net (code "50") (name "Net-(U$2M-1)") (class "Default")
      (node (ref "D49") (pin "A") (pinfunction "A_A") (pintype "passive"))
      (node (ref "D51") (pin "A") (pinfunction "A_A") (pintype "passive"))
      (node (ref "U$2") (pin "P2") (pinfunction "1_P2") (pintype "bidirectional"))
    )
    (net (code "51") (name "Net-(U$2N-1)") (class "Default")
      (node (ref "D31") (pin "C") (pinfunction "C_C") (pintype "passive"))
      (node (ref "D34") (pin "C") (pinfunction "C_C") (pintype "passive"))
      (node (ref "U$2") (pin "R2") (pinfunction "1_R2") (pintype "bidirectional"))
    )
    (net (code "52") (name "Net-(U$2O-1)") (class "Default")
      (node (ref "D59") (pin "A") (pinfunction "A_A") (pintype "passive"))
      (node (ref "D61") (pin "A") (pinfunction "A_A") (pintype "passive"))
      (node (ref "U$2") (pin "S2") (pinfunction "1_S2") (pintype "bidirectional"))
    )
    (net (code "53") (name "Net-(U$2Q-1)") (class "Default")
      (node (ref "D70") (pin "A") (pinfunction "A_A") (pintype "passive"))
      (node (ref "D73") (pin "A") (pinfunction "A_A") (pintype "passive"))
      (node (ref "U$2") (pin "U2") (pinfunction "1_U2") (pintype "bidirectional"))
    )
    (net (code "54") (name "Net-(U$2R-1)") (class "Default")
      (node (ref "D71") (pin "A") (pinfunction "A_A") (pintype "passive"))
      (node (ref "D72") (pin "A") (pinfunction "A_A") (pintype "passive"))
      (node (ref "U$2") (pin "V2") (pinfunction "1_V2") (pintype "bidirectional"))
    )
  )
)
